# boot_rig_atmega.net
KiCad netlist of a schematic drawn in EAGLE
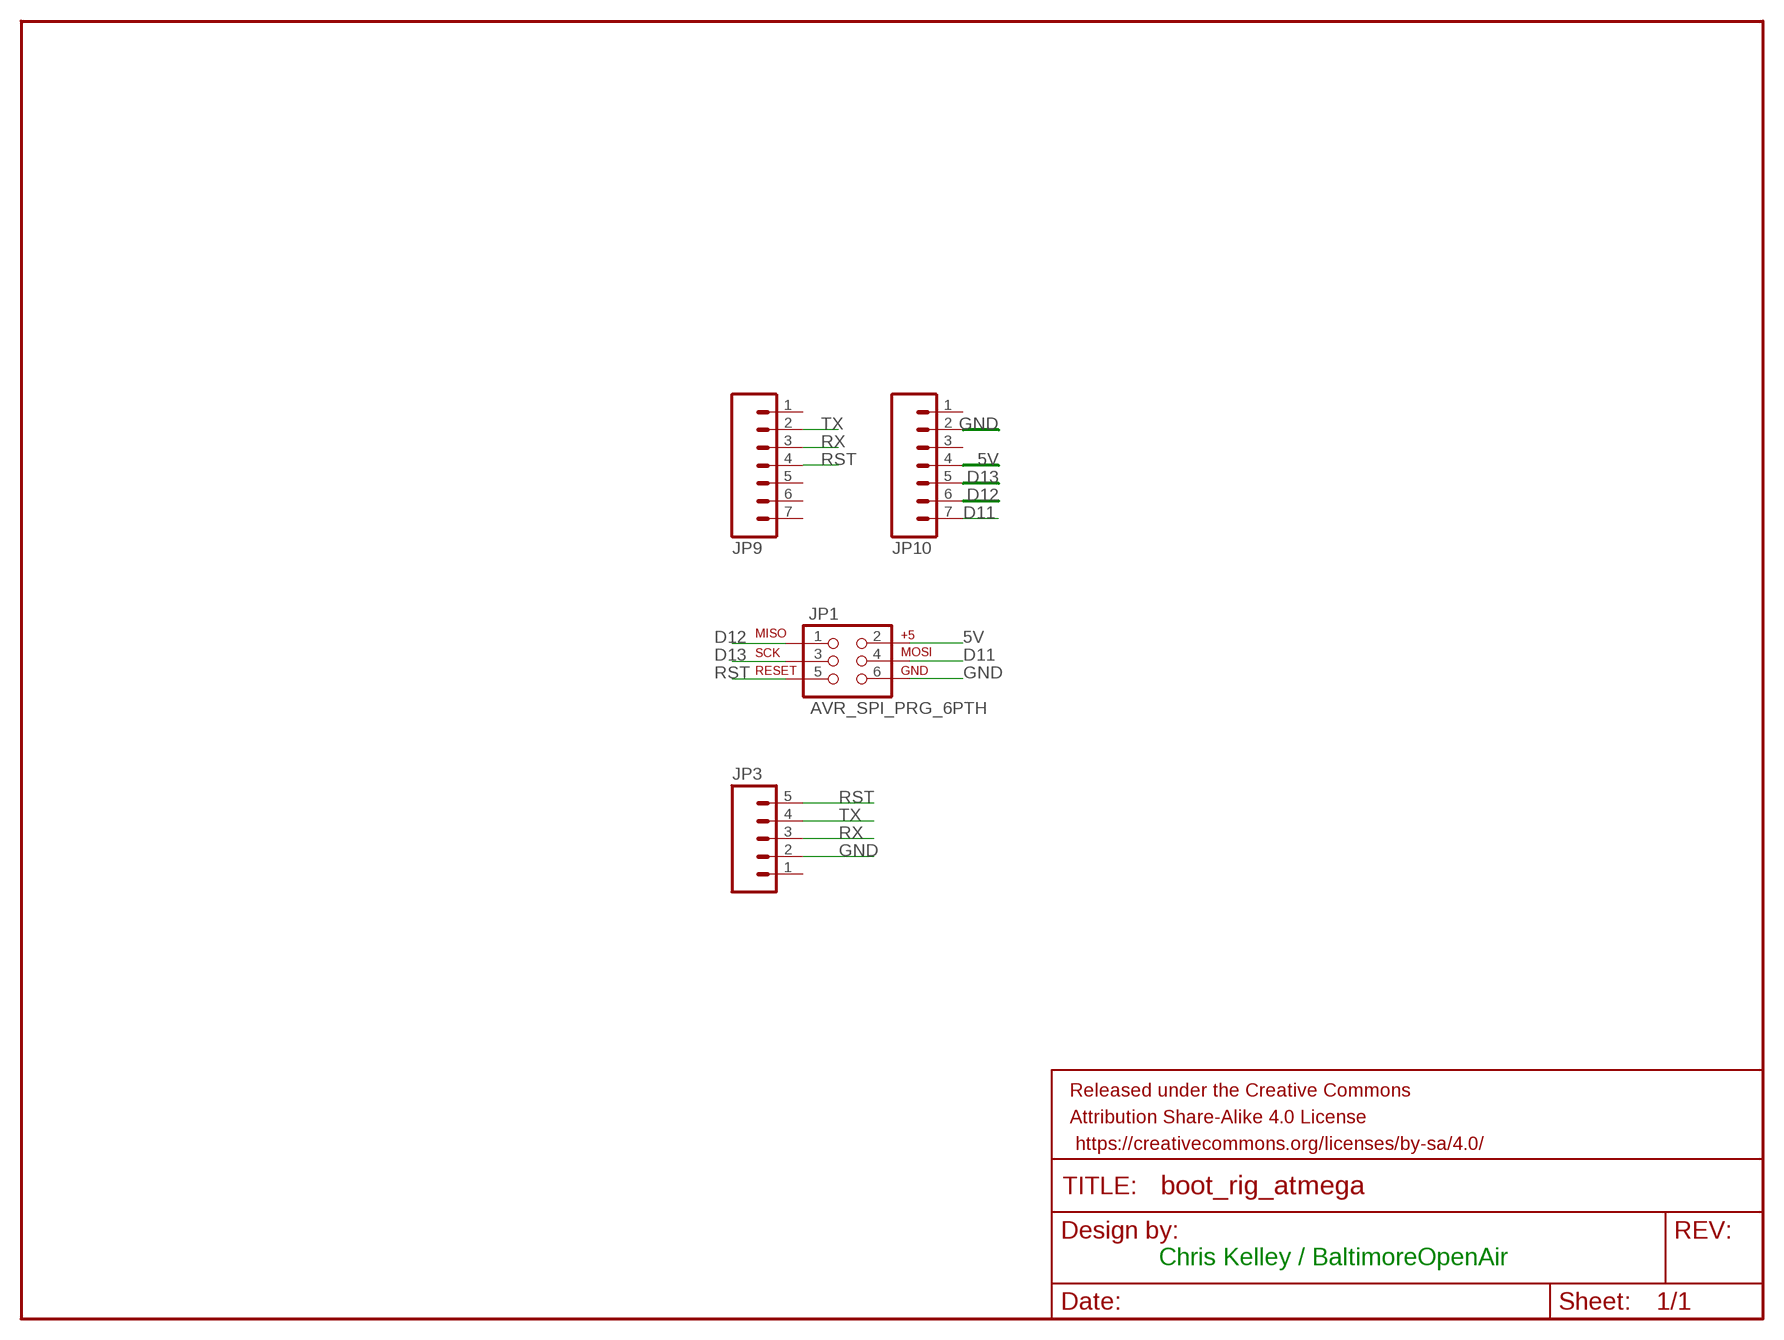
[diagram p0: schematic, sheet 1]

(export (version "E")
  (design (tool "Eeschema 10.0.6"))
  (components
    (comp (ref "FRAME1")
      (value "FRAME-LETTER")
      (footprint "eagle-import:CREATIVE_COMMONS")
      (libsource (lib "eagle-import") (part "FRAME-LETTER"))
    )
    (comp (ref "JP1")
      (value "AVR_SPI_PRG_6PTH")
      (footprint "eagle-import:2X3")
      (libsource (lib "eagle-import") (part "AVR_SPI_PRG_6PTH"))
    )
    (comp (ref "JP3")
      (value "M05PTH")
      (footprint "eagle-import:1X05")
      (libsource (lib "eagle-import") (part "M05PTH"))
    )
    (comp (ref "JP9")
      (value "M07")
      (footprint "eagle-import:1X07")
      (libsource (lib "eagle-import") (part "M07"))
    )
    (comp (ref "JP10")
      (value "M07")
      (footprint "eagle-import:1X07")
      (libsource (lib "eagle-import") (part "M07"))
    )
  )
  (nets
    (net (code "1") (name "/5V") (class "Default")
      (node (ref "JP1") (pin "2") (pinfunction "2_2") (pintype "passive"))
      (node (ref "JP10") (pin "4") (pinfunction "4_4") (pintype "passive"))
    )
    (net (code "2") (name "/D11") (class "Default")
      (node (ref "JP1") (pin "4") (pinfunction "4_4") (pintype "passive"))
      (node (ref "JP10") (pin "7") (pinfunction "7_7") (pintype "passive"))
    )
    (net (code "3") (name "/D12") (class "Default")
      (node (ref "JP1") (pin "1") (pinfunction "1_1") (pintype "passive"))
      (node (ref "JP10") (pin "6") (pinfunction "6_6") (pintype "passive"))
    )
    (net (code "4") (name "/D13") (class "Default")
      (node (ref "JP1") (pin "3") (pinfunction "3_3") (pintype "passive"))
      (node (ref "JP10") (pin "5") (pinfunction "5_5") (pintype "passive"))
    )
    (net (code "5") (name "/GND") (class "Default")
      (node (ref "JP1") (pin "6") (pinfunction "6_6") (pintype "passive"))
      (node (ref "JP10") (pin "2") (pinfunction "2_2") (pintype "passive"))
      (node (ref "JP3") (pin "2") (pinfunction "2_2") (pintype "passive"))
    )
    (net (code "6") (name "/RST") (class "Default")
      (node (ref "JP1") (pin "5") (pinfunction "5_5") (pintype "passive"))
      (node (ref "JP3") (pin "5") (pinfunction "5_5") (pintype "passive"))
      (node (ref "JP9") (pin "4") (pinfunction "4_4") (pintype "passive"))
    )
    (net (code "7") (name "/RX") (class "Default")
      (node (ref "JP3") (pin "3") (pinfunction "3_3") (pintype "passive"))
      (node (ref "JP9") (pin "3") (pinfunction "3_3") (pintype "passive"))
    )
    (net (code "8") (name "/TX") (class "Default")
      (node (ref "JP3") (pin "4") (pinfunction "4_4") (pintype "passive"))
      (node (ref "JP9") (pin "2") (pinfunction "2_2") (pintype "passive"))
    )
    (net (code "9") (name "unconnected-(JP3-Pad1)") (class "Default")
      (node (ref "JP3") (pin "1") (pinfunction "1_1") (pintype "passive"))
    )
    (net (code "10") (name "unconnected-(JP9-Pad1)") (class "Default")
      (node (ref "JP9") (pin "1") (pinfunction "1_1") (pintype "passive"))
    )
    (net (code "11") (name "unconnected-(JP9-Pad5)") (class "Default")
      (node (ref "JP9") (pin "5") (pinfunction "5_5") (pintype "passive"))
    )
    (net (code "12") (name "unconnected-(JP9-Pad6)") (class "Default")
      (node (ref "JP9") (pin "6") (pinfunction "6_6") (pintype "passive"))
    )
    (net (code "13") (name "unconnected-(JP9-Pad7)") (class "Default")
      (node (ref "JP9") (pin "7") (pinfunction "7_7") (pintype "passive"))
    )
    (net (code "14") (name "unconnected-(JP10-Pad1)") (class "Default")
      (node (ref "JP10") (pin "1") (pinfunction "1_1") (pintype "passive"))
    )
    (net (code "15") (name "unconnected-(JP10-Pad3)") (class "Default")
      (node (ref "JP10") (pin "3") (pinfunction "3_3") (pintype "passive"))
    )
  )
)
